# openSX70_ALADDIN_V398SEEED_20180219.net
KiCad netlist of a schematic drawn in EAGLE
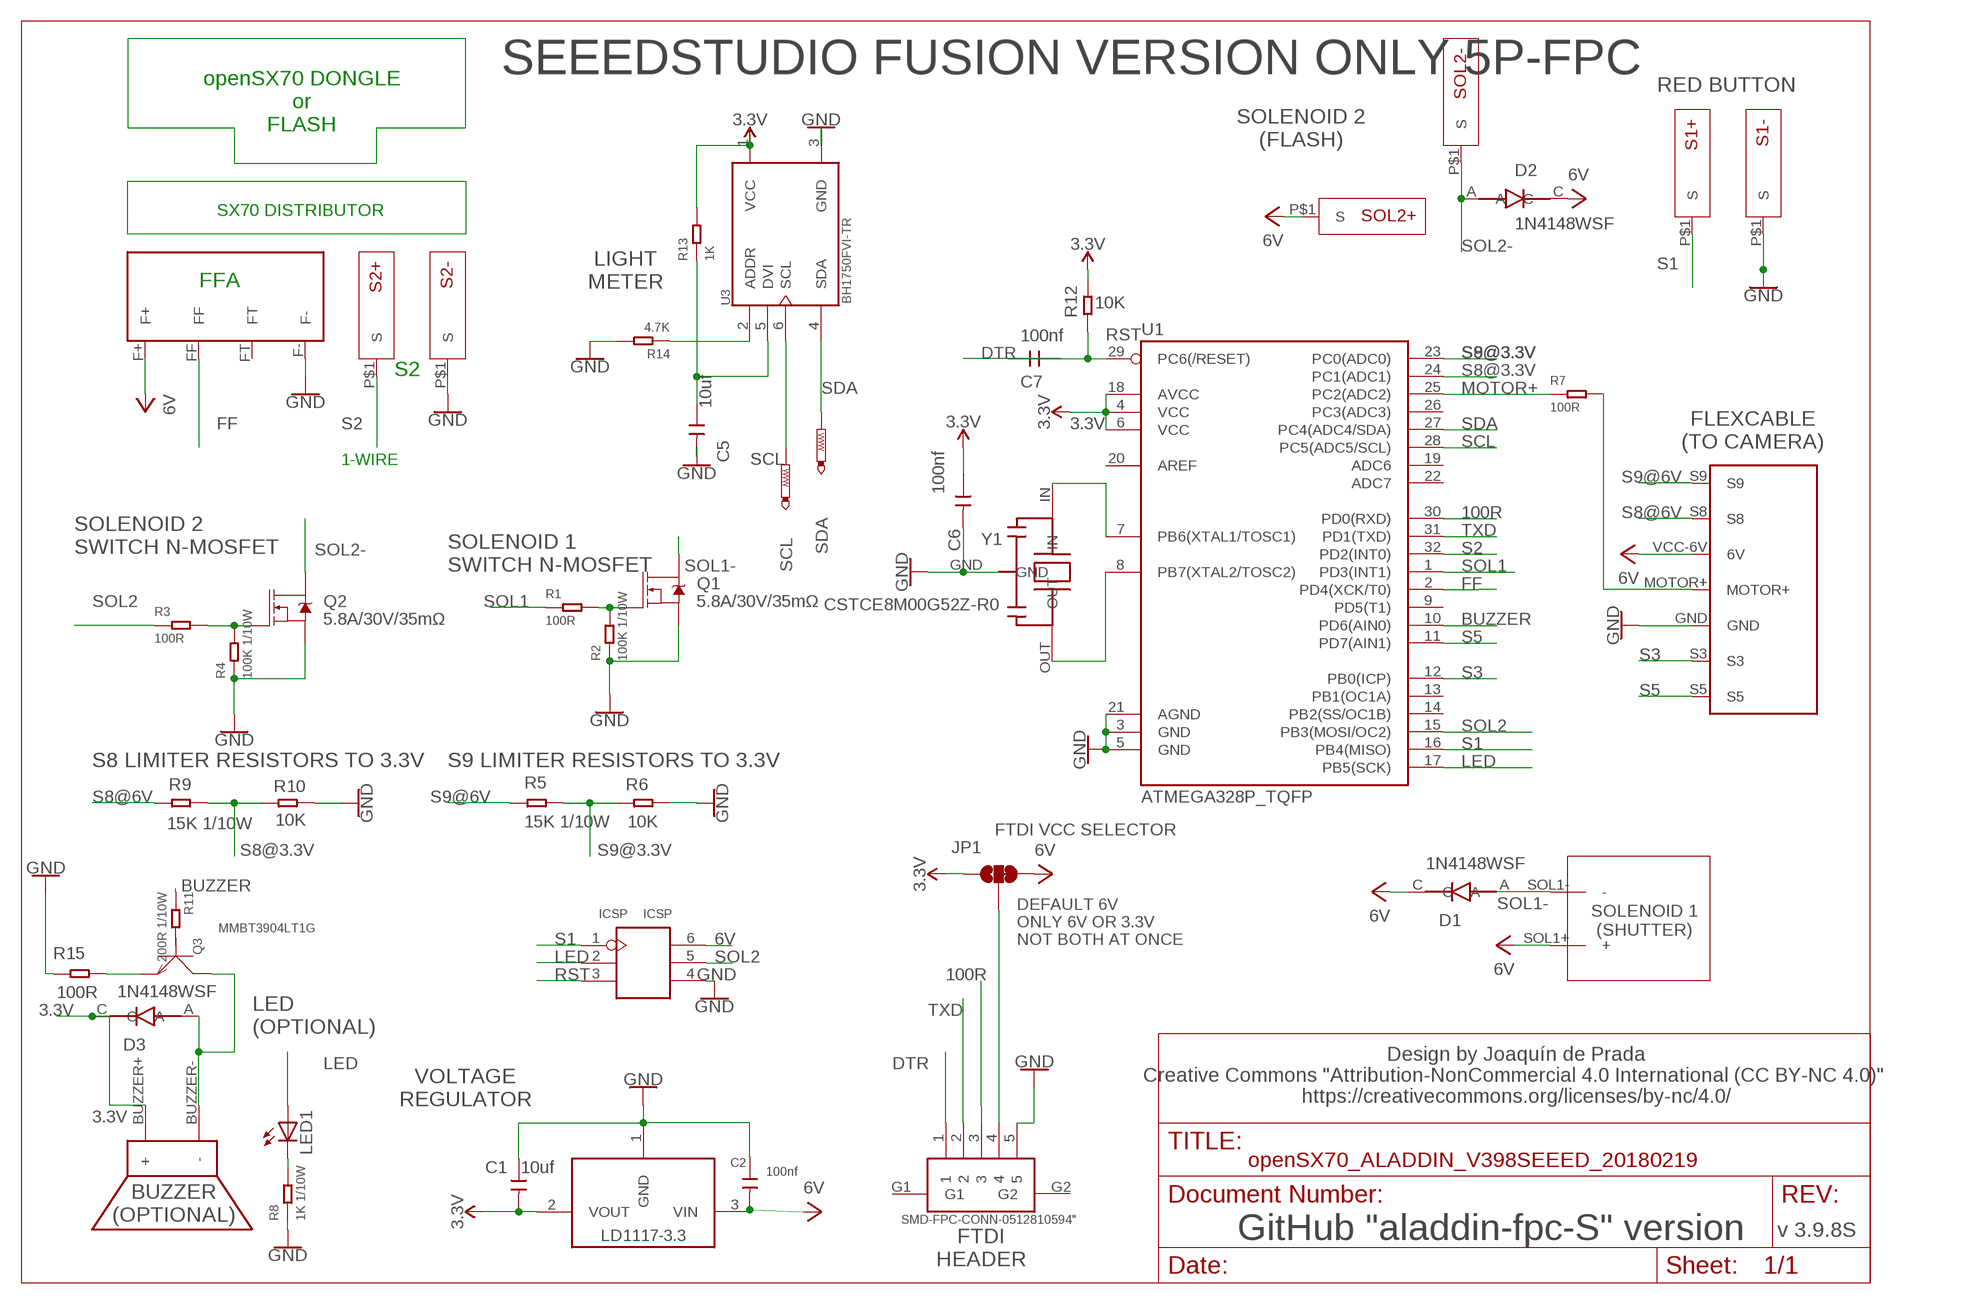
[diagram p0: schematic, sheet 1]

(export (version "E")
  (design (tool "Eeschema 10.0.6"))
  (components
    (comp (ref "C1")
      (value "10uf")
      (footprint "eagle-import:C0603")
      (fields (field (name "MPN") "CC0603KRX5R6BB106"))
      (libsource (lib "eagle-import") (part "CERAMIC-10UF-10V-10%-X5R(0603)"))
    )
    (comp (ref "C2")
      (value "100nf")
      (footprint "eagle-import:C0603")
      (fields (field (name "MPN") "CC0603KRX7R9BB104"))
      (libsource (lib "eagle-import") (part "CERAMIC-100NF-50V-10%-X7R(0603)"))
    )
    (comp (ref "C5")
      (value "10uf")
      (footprint "eagle-import:C0603")
      (fields (field (name "MPN") "CC0603KRX5R6BB106"))
      (libsource (lib "eagle-import") (part "CERAMIC-10UF-10V-10%-X5R(0603)"))
    )
    (comp (ref "C6")
      (value "100nf")
      (footprint "eagle-import:C0603")
      (fields (field (name "MPN") "CC0603KRX7R9BB104"))
      (libsource (lib "eagle-import") (part "CERAMIC-100NF-50V-10%-X7R(0603)"))
    )
    (comp (ref "C7")
      (value "100nf")
      (footprint "eagle-import:C0603")
      (fields (field (name "MPN") "CC0603KRX7R9BB104"))
      (libsource (lib "eagle-import") (part "CERAMIC-100NF-50V-10%-X7R(0603)"))
    )
    (comp (ref "D1")
      (value "1N4148WSF")
      (footprint "eagle-import:SODFL2512X100N")
      (fields (field (name "MANUFACTURER") "Fairchild Semiconductor"))
      (libsource (lib "eagle-import") (part "1N4148WS"))
    )
    (comp (ref "D2")
      (value "1N4148WSF")
      (footprint "eagle-import:SODFL2512X100N")
      (fields (field (name "MANUFACTURER") "Fairchild Semiconductor"))
      (libsource (lib "eagle-import") (part "1N4148WS"))
    )
    (comp (ref "D3")
      (value "1N4148WSF")
      (footprint "eagle-import:SODFL2512X100N")
      (fields (field (name "MANUFACTURER") "Fairchild Semiconductor"))
      (libsource (lib "eagle-import") (part "1N4148WS"))
    )
    (comp (ref "ICSP")
      (value "ICSP")
      (footprint "eagle-import:H2X3-2.54")
      (libsource (lib "eagle-import") (part "ICSP"))
    )
    (comp (ref "JP1")
      (value "FTDI VCC SELECTOR")
      (footprint "eagle-import:SMT-JUMPER_3_1-NC_TRACE_SILK")
      (libsource (lib "eagle-import") (part "JUMPER-SMT_3_1-NC_TRACE_SILK"))
    )
    (comp (ref "LD11172.5V")
      (value "LD1117 2.5V")
      (footprint "eagle-import:SOT223")
      (fields (field (name "MF") "Advanced Monolithic Systems") (field (name "MP") "AMS1117-5.0"))
      (libsource (lib "eagle-import") (part "LD1117-3.3"))
    )
    (comp (ref "LED1")
      (value "LEDCHIPLED_0805")
      (footprint "eagle-import:CHIPLED_0805")
      (libsource (lib "eagle-import") (part "LEDCHIPLED_0805"))
    )
    (comp (ref "Q1")
      (value "5.8A/30V/35mΩ")
      (footprint "eagle-import:SOT23-3")
      (libsource (lib "eagle-import") (part "MOSFET-NCH-AO3404A"))
    )
    (comp (ref "Q2")
      (value "5.8A/30V/35mΩ")
      (footprint "eagle-import:SOT23-3")
      (libsource (lib "eagle-import") (part "MOSFET-NCH-AO3404A"))
    )
    (comp (ref "Q3")
      (value "MMBT3904LT1G")
      (footprint "eagle-import:SOT-23")
      (libsource (lib "eagle-import") (part "SMD-TRANSISTORS-NPN-40V-200MA-MMBT3904LT1G(SOT-23)"))
    )
    (comp (ref "R1")
      (value "100R")
      (footprint "eagle-import:R0603")
      (fields (field (name "MPN") "RC0603JR-07100RL"))
      (libsource (lib "eagle-import") (part "SMD-RES-100R-5%-1/10W(0603)"))
    )
    (comp (ref "R2")
      (value "100K 1/10W")
      (footprint "eagle-import:R0603")
      (fields (field (name "MPN") "RC0603JR-07100KL"))
      (libsource (lib "eagle-import") (part "SMD-RES-100K-5%-1/10W(0603)"))
    )
    (comp (ref "R3")
      (value "100R")
      (footprint "eagle-import:R0603")
      (fields (field (name "MPN") "RC0603JR-07100RL"))
      (libsource (lib "eagle-import") (part "SMD-RES-100R-5%-1/10W(0603)"))
    )
    (comp (ref "R4")
      (value "100K 1/10W")
      (footprint "eagle-import:R0603")
      (fields (field (name "MPN") "RC0603JR-07100KL"))
      (libsource (lib "eagle-import") (part "SMD-RES-100K-5%-1/10W(0603)"))
    )
    (comp (ref "R5")
      (value "15K 1/10W")
      (footprint "eagle-import:R0603")
      (fields (field (name "MPN") "RC0603FR-0715KL"))
      (libsource (lib "eagle-import") (part "SMD-RES-15K-1%-1/10W(0603)"))
    )
    (comp (ref "R6")
      (value "10K")
      (footprint "eagle-import:R0603")
      (fields (field (name "MPN") "RC0603FR-0710KL"))
      (libsource (lib "eagle-import") (part "SMD-RES-10K-1%-1/10W(0603)"))
    )
    (comp (ref "R7")
      (value "100R")
      (footprint "eagle-import:R0603")
      (fields (field (name "MPN") "RC0603JR-07100RL"))
      (libsource (lib "eagle-import") (part "SMD-RES-100R-5%-1/10W(0603)"))
    )
    (comp (ref "R8")
      (value "1K 1/10W")
      (footprint "eagle-import:R0603")
      (fields (field (name "MPN") "RC0603JR-071KL"))
      (libsource (lib "eagle-import") (part "SMD-RES-1K-5%-1/10W(0603)"))
    )
    (comp (ref "R9")
      (value "15K 1/10W")
      (footprint "eagle-import:R0603")
      (fields (field (name "MPN") "RC0603FR-0715KL"))
      (libsource (lib "eagle-import") (part "SMD-RES-15K-1%-1/10W(0603)"))
    )
    (comp (ref "R10")
      (value "10K")
      (footprint "eagle-import:R0603")
      (fields (field (name "MPN") "RC0603FR-0710KL"))
      (libsource (lib "eagle-import") (part "SMD-RES-10K-1%-1/10W(0603)"))
    )
    (comp (ref "R11")
      (value "200R 1/10W")
      (footprint "eagle-import:R0603")
      (fields (field (name "MPN") "RC0603JR-07200RL"))
      (libsource (lib "eagle-import") (part "SMD-RES-200R-5%-1/10W(0603)"))
    )
    (comp (ref "R12")
      (value "10K")
      (footprint "eagle-import:R0603")
      (fields (field (name "MPN") "RC0603FR-0710KL"))
      (libsource (lib "eagle-import") (part "SMD-RES-10K-1%-1/10W(0603)"))
    )
    (comp (ref "R13")
      (value "1K")
      (footprint "eagle-import:R0603")
      (fields (field (name "MPN") "RC0603FR-071KL"))
      (libsource (lib "eagle-import") (part "SMD-RES-1K-1%-1/10W(0603)"))
    )
    (comp (ref "R14")
      (value "4.7K")
      (footprint "eagle-import:R0603")
      (fields (field (name "MPN") "RC0603JR-074K7L"))
      (libsource (lib "eagle-import") (part "SMD-RES-4.7K-5%-1/10W(0603)"))
    )
    (comp (ref "R15")
      (value "100R")
      (footprint "eagle-import:R0603")
      (fields (field (name "MPN") "RC0603JR-07100RL"))
      (libsource (lib "eagle-import") (part "SMD-RES-100R-5%-1/10W(0603)"))
    )
    (comp (ref "S1+")
      (value "SX70-S-PAD-NEW")
      (footprint "eagle-import:SX70-S-PAD2")
      (libsource (lib "eagle-import") (part "SX70-S-PAD-NEW"))
    )
    (comp (ref "S1-")
      (value "SX70-S-PAD-NEW")
      (footprint "eagle-import:SX70-S-PAD2")
      (libsource (lib "eagle-import") (part "SX70-S-PAD-NEW"))
    )
    (comp (ref "S2+")
      (value "SX70-S-PAD-NEW")
      (footprint "eagle-import:SX70-S-PAD2")
      (libsource (lib "eagle-import") (part "SX70-S-PAD-NEW"))
    )
    (comp (ref "S2-")
      (value "SX70-S-PAD-NEW")
      (footprint "eagle-import:SX70-S-PAD2")
      (libsource (lib "eagle-import") (part "SX70-S-PAD-NEW"))
    )
    (comp (ref "SCL")
      (value "PTR1TP08R")
      (footprint "eagle-import:TP08R")
      (libsource (lib "eagle-import") (part "PTR1TP08R"))
    )
    (comp (ref "SDA")
      (value "PTR1TP08R")
      (footprint "eagle-import:TP08R")
      (libsource (lib "eagle-import") (part "PTR1TP08R"))
    )
    (comp (ref "SOL1")
      (value "SX70-SOLENOID1-2PADS")
      (footprint "eagle-import:SX70-SOLENOID1-2")
      (libsource (lib "eagle-import") (part "SX70-SOLENOID1-2PADS"))
    )
    (comp (ref "SOL2+")
      (value "SX70-S-PAD-NEW")
      (footprint "eagle-import:SX70-S-PAD2")
      (libsource (lib "eagle-import") (part "SX70-S-PAD-NEW"))
    )
    (comp (ref "SOL2-")
      (value "SX70-S-PAD-NEW")
      (footprint "eagle-import:SX70-S-PAD2")
      (libsource (lib "eagle-import") (part "SX70-S-PAD-NEW"))
    )
    (comp (ref "U$1")
      (value "SX70-7-PAD")
      (footprint "eagle-import:SX70-7-PAD")
      (libsource (lib "eagle-import") (part "SX70-7-PAD"))
    )
    (comp (ref "U$2")
      (value "FFA")
      (footprint "eagle-import:FFA-PAD-PACKAGE")
      (libsource (lib "eagle-import") (part "SX70-FFA-PAD"))
    )
    (comp (ref "U$3")
      (value "CSET8-5G_V2")
      (footprint "eagle-import:CSET8-5G_PACKAGE")
      (libsource (lib "eagle-import") (part "CSET8-5G_V2"))
    )
    (comp (ref "U$4")
      (value "SMD-FPC-CONN-0512810594\"")
      (footprint "eagle-import:51281-0594")
      (libsource (lib "eagle-import") (part "SMD-FPC-CONN-0512810594{dblquote}"))
    )
    (comp (ref "U1")
      (value "ATMEGA328P_TQFP")
      (footprint "eagle-import:TQFP32-08")
      (libsource (lib "eagle-import") (part "ATMEGA328P_TQFP"))
    )
    (comp (ref "U3")
      (value "BH1750FVI-TR")
      (footprint "eagle-import:SOTFL50P300X75-6N")
      (fields (field (name "MF") "Rohm"))
      (libsource (lib "eagle-import") (part "BH1750FVI-TR"))
    )
    (comp (ref "Y1")
      (value "CSTCE8M00G52Z-R0")
      (footprint "eagle-import:CFP95P160X100-3N")
      (fields (field (name "MF") "Murata") (field (name "MP") "CSTCE16M0V53-R0"))
      (libsource (lib "eagle-import") (part "CSTCE16M0V53-R0"))
    )
  )
  (nets
    (net (code "1") (name "/100R") (class "Default")
      (node (ref "U$4") (pin "3") (pinfunction "3_3") (pintype "bidirectional"))
      (node (ref "U1") (pin "30") (pinfunction "PD0(RXD)_30") (pintype "bidirectional"))
    )
    (net (code "2") (name "/BUZZER") (class "Default")
      (node (ref "R11") (pin "1") (pinfunction "1_1") (pintype "passive"))
      (node (ref "U1") (pin "10") (pinfunction "PD6(AIN0)_10") (pintype "bidirectional"))
    )
    (net (code "3") (name "/DTR") (class "Default")
      (node (ref "C7") (pin "1") (pinfunction "1_1") (pintype "passive"))
      (node (ref "U$4") (pin "1") (pinfunction "1_1") (pintype "bidirectional"))
    )
    (net (code "4") (name "/FF") (class "Default")
      (node (ref "U$2") (pin "FF") (pinfunction "FF_FF") (pintype "bidirectional"))
      (node (ref "U1") (pin "2") (pinfunction "PD4(XCK/T0)_2") (pintype "bidirectional"))
    )
    (net (code "5") (name "/LED") (class "Default")
      (node (ref "ICSP") (pin "2") (pinfunction "SCK_2") (pintype "bidirectional"))
      (node (ref "LED1") (pin "A") (pinfunction "A_A") (pintype "passive"))
      (node (ref "U1") (pin "17") (pinfunction "PB5(SCK)_17") (pintype "bidirectional"))
    )
    (net (code "6") (name "/MOTOR+") (class "Default")
      (node (ref "R7") (pin "1") (pinfunction "1_1") (pintype "passive"))
      (node (ref "U1") (pin "25") (pinfunction "PC2(ADC2)_25") (pintype "bidirectional"))
    )
    (net (code "7") (name "/RST") (class "Default")
      (node (ref "C7") (pin "2") (pinfunction "2_2") (pintype "passive"))
      (node (ref "ICSP") (pin "3") (pinfunction "RST_3") (pintype "bidirectional"))
      (node (ref "R12") (pin "1") (pinfunction "1_1") (pintype "passive"))
      (node (ref "U1") (pin "29") (pinfunction "PC6(/RESET)_29") (pintype "bidirectional"))
    )
    (net (code "8") (name "/S1") (class "Default")
      (node (ref "ICSP") (pin "1") (pinfunction "MISO_1") (pintype "bidirectional"))
      (node (ref "S1+") (pin "P$1") (pinfunction "S_P$1") (pintype "bidirectional"))
      (node (ref "U1") (pin "16") (pinfunction "PB4(MISO)_16") (pintype "bidirectional"))
    )
    (net (code "9") (name "/S2") (class "Default")
      (node (ref "S2+") (pin "P$1") (pinfunction "S_P$1") (pintype "bidirectional"))
      (node (ref "U1") (pin "32") (pinfunction "PD2(INT0)_32") (pintype "bidirectional"))
    )
    (net (code "10") (name "/S3") (class "Default")
      (node (ref "U$1") (pin "S3") (pinfunction "S3_S3") (pintype "bidirectional"))
      (node (ref "U1") (pin "12") (pinfunction "PB0(ICP)_12") (pintype "bidirectional"))
    )
    (net (code "11") (name "/S5") (class "Default")
      (node (ref "U$1") (pin "S5") (pinfunction "S5_S5") (pintype "bidirectional"))
      (node (ref "U1") (pin "11") (pinfunction "PD7(AIN1)_11") (pintype "bidirectional"))
    )
    (net (code "12") (name "/S8@3.3V") (class "Default")
      (node (ref "R10") (pin "1") (pinfunction "1_1") (pintype "passive"))
      (node (ref "R9") (pin "2") (pinfunction "2_2") (pintype "passive"))
      (node (ref "U1") (pin "24") (pinfunction "PC1(ADC1)_24") (pintype "bidirectional"))
    )
    (net (code "13") (name "/S8@6V") (class "Default")
      (node (ref "R9") (pin "1") (pinfunction "1_1") (pintype "passive"))
      (node (ref "U$1") (pin "S8") (pinfunction "S8_S8") (pintype "bidirectional"))
    )
    (net (code "14") (name "/S9@3.3V") (class "Default")
      (node (ref "R5") (pin "2") (pinfunction "2_2") (pintype "passive"))
      (node (ref "R6") (pin "1") (pinfunction "1_1") (pintype "passive"))
      (node (ref "U1") (pin "23") (pinfunction "PC0(ADC0)_23") (pintype "bidirectional"))
    )
    (net (code "15") (name "/S9@6V") (class "Default")
      (node (ref "R5") (pin "1") (pinfunction "1_1") (pintype "passive"))
      (node (ref "U$1") (pin "S9") (pinfunction "S9_S9") (pintype "bidirectional"))
    )
    (net (code "16") (name "/SCL") (class "Default")
      (node (ref "SCL") (pin "TP") (pinfunction "TP_TP") (pintype "input"))
      (node (ref "U1") (pin "28") (pinfunction "PC5(ADC5/SCL)_28") (pintype "bidirectional"))
      (node (ref "U3") (pin "6") (pinfunction "SCL_6") (pintype "input"))
    )
    (net (code "17") (name "/SDA") (class "Default")
      (node (ref "SDA") (pin "TP") (pinfunction "TP_TP") (pintype "input"))
      (node (ref "U1") (pin "27") (pinfunction "PC4(ADC4/SDA)_27") (pintype "bidirectional"))
      (node (ref "U3") (pin "4") (pinfunction "SDA_4") (pintype "bidirectional"))
    )
    (net (code "18") (name "/SOL1") (class "Default")
      (node (ref "R1") (pin "1") (pinfunction "1_1") (pintype "passive"))
      (node (ref "U1") (pin "1") (pinfunction "PD3(INT1)_1") (pintype "bidirectional"))
    )
    (net (code "19") (name "/SOL1-") (class "Default")
      (node (ref "D1") (pin "A") (pinfunction "A_A") (pintype "passive"))
      (node (ref "Q1") (pin "3") (pinfunction "D_3") (pintype "bidirectional"))
      (node (ref "SOL1") (pin "SOL1-") (pinfunction "-_SOL1-") (pintype "bidirectional"))
    )
    (net (code "20") (name "/SOL2") (class "Default")
      (node (ref "ICSP") (pin "5") (pinfunction "MOSI_5") (pintype "bidirectional"))
      (node (ref "R3") (pin "1") (pinfunction "1_1") (pintype "passive"))
      (node (ref "U1") (pin "15") (pinfunction "PB3(MOSI/OC2)_15") (pintype "bidirectional"))
    )
    (net (code "21") (name "/SOL2-") (class "Default")
      (node (ref "D2") (pin "A") (pinfunction "A_A") (pintype "passive"))
      (node (ref "Q2") (pin "3") (pinfunction "D_3") (pintype "bidirectional"))
      (node (ref "SOL2-") (pin "P$1") (pinfunction "S_P$1") (pintype "bidirectional"))
    )
    (net (code "22") (name "/TXD") (class "Default")
      (node (ref "U$4") (pin "2") (pinfunction "2_2") (pintype "bidirectional"))
      (node (ref "U1") (pin "31") (pinfunction "PD1(TXD)_31") (pintype "bidirectional"))
    )
    (net (code "23") (name "3.3V") (class "Default")
      (node (ref "C1") (pin "2") (pinfunction "2_2") (pintype "passive"))
      (node (ref "C6") (pin "1") (pinfunction "1_1") (pintype "passive"))
      (node (ref "D3") (pin "C") (pinfunction "C_C") (pintype "passive"))
      (node (ref "JP1") (pin "1") (pinfunction "1_1") (pintype "passive"))
      (node (ref "LD11172.5V") (pin "2") (pinfunction "VOUT_2") (pintype "bidirectional"))
      (node (ref "R12") (pin "2") (pinfunction "2_2") (pintype "passive"))
      (node (ref "R13") (pin "2") (pinfunction "2_2") (pintype "passive"))
      (node (ref "U$3") (pin "BUZZER+") (pinfunction "+_BUZZER+") (pintype "bidirectional"))
      (node (ref "U1") (pin "18") (pinfunction "AVCC_18") (pintype "bidirectional"))
      (node (ref "U1") (pin "4") (pinfunction "VCC_4") (pintype "bidirectional"))
      (node (ref "U1") (pin "6") (pinfunction "VCC_6") (pintype "bidirectional"))
      (node (ref "U3") (pin "1") (pinfunction "VCC_1") (pintype "power_in"))
    )
    (net (code "24") (name "6V") (class "Default")
      (node (ref "C2") (pin "2") (pinfunction "2_2") (pintype "passive"))
      (node (ref "D1") (pin "C") (pinfunction "C_C") (pintype "passive"))
      (node (ref "D2") (pin "C") (pinfunction "C_C") (pintype "passive"))
      (node (ref "ICSP") (pin "6") (pinfunction "VCC_6") (pintype "bidirectional"))
      (node (ref "JP1") (pin "3") (pinfunction "3_3") (pintype "passive"))
      (node (ref "LD11172.5V") (pin "3") (pinfunction "VIN_3") (pintype "bidirectional"))
      (node (ref "SOL1") (pin "SOL1+") (pinfunction "+_SOL1+") (pintype "bidirectional"))
      (node (ref "SOL2+") (pin "P$1") (pinfunction "S_P$1") (pintype "bidirectional"))
      (node (ref "U$1") (pin "VCC-6V") (pinfunction "6V_VCC-6V") (pintype "bidirectional"))
      (node (ref "U$2") (pin "F+") (pinfunction "F+_F+") (pintype "bidirectional"))
    )
    (net (code "25") (name "GND") (class "Default")
      (node (ref "C1") (pin "1") (pinfunction "1_1") (pintype "passive"))
      (node (ref "C2") (pin "1") (pinfunction "1_1") (pintype "passive"))
      (node (ref "C5") (pin "2") (pinfunction "2_2") (pintype "passive"))
      (node (ref "C6") (pin "2") (pinfunction "2_2") (pintype "passive"))
      (node (ref "ICSP") (pin "4") (pinfunction "GND_4") (pintype "bidirectional"))
      (node (ref "LD11172.5V") (pin "1") (pinfunction "GND_1") (pintype "bidirectional"))
      (node (ref "Q1") (pin "2") (pinfunction "S_2") (pintype "bidirectional"))
      (node (ref "Q2") (pin "2") (pinfunction "S_2") (pintype "bidirectional"))
      (node (ref "R10") (pin "2") (pinfunction "2_2") (pintype "passive"))
      (node (ref "R14") (pin "2") (pinfunction "2_2") (pintype "passive"))
      (node (ref "R15") (pin "1") (pinfunction "1_1") (pintype "passive"))
      (node (ref "R2") (pin "1") (pinfunction "1_1") (pintype "passive"))
      (node (ref "R4") (pin "1") (pinfunction "1_1") (pintype "passive"))
      (node (ref "R6") (pin "2") (pinfunction "2_2") (pintype "passive"))
      (node (ref "R8") (pin "1") (pinfunction "1_1") (pintype "passive"))
      (node (ref "S1-") (pin "P$1") (pinfunction "S_P$1") (pintype "bidirectional"))
      (node (ref "S2-") (pin "P$1") (pinfunction "S_P$1") (pintype "bidirectional"))
      (node (ref "U$1") (pin "GND") (pinfunction "GND_GND") (pintype "bidirectional"))
      (node (ref "U$2") (pin "F-") (pinfunction "F-_F-") (pintype "bidirectional"))
      (node (ref "U$4") (pin "5") (pinfunction "5_5") (pintype "bidirectional"))
      (node (ref "U1") (pin "21") (pinfunction "AGND_21") (pintype "bidirectional"))
      (node (ref "U1") (pin "3") (pinfunction "GND_3") (pintype "bidirectional"))
      (node (ref "U1") (pin "5") (pinfunction "GND_5") (pintype "bidirectional"))
      (node (ref "U3") (pin "3") (pinfunction "GND_3") (pintype "power_in"))
      (node (ref "Y1") (pin "GND") (pinfunction "GND_GND") (pintype "passive"))
    )
    (net (code "26") (name "Net-(JP1-Pad2)") (class "Default")
      (node (ref "JP1") (pin "2") (pinfunction "2_2") (pintype "passive"))
      (node (ref "U$4") (pin "4") (pinfunction "4_4") (pintype "bidirectional"))
    )
    (net (code "27") (name "Net-(LED1-PadC)") (class "Default")
      (node (ref "LED1") (pin "C") (pinfunction "C_C") (pintype "passive"))
      (node (ref "R8") (pin "2") (pinfunction "2_2") (pintype "passive"))
    )
    (net (code "28") (name "Net-(Q1-G)") (class "Default")
      (node (ref "Q1") (pin "1") (pinfunction "G_1") (pintype "bidirectional"))
      (node (ref "R1") (pin "2") (pinfunction "2_2") (pintype "passive"))
      (node (ref "R2") (pin "2") (pinfunction "2_2") (pintype "passive"))
    )
    (net (code "29") (name "Net-(Q2-G)") (class "Default")
      (node (ref "Q2") (pin "1") (pinfunction "G_1") (pintype "bidirectional"))
      (node (ref "R3") (pin "2") (pinfunction "2_2") (pintype "passive"))
      (node (ref "R4") (pin "2") (pinfunction "2_2") (pintype "passive"))
    )
    (net (code "30") (name "Net-(Q3-B)") (class "Default")
      (node (ref "Q3") (pin "1") (pinfunction "B_1") (pintype "passive"))
      (node (ref "R11") (pin "2") (pinfunction "2_2") (pintype "passive"))
    )
    (net (code "31") (name "Net-(Q3-C)") (class "Default")
      (node (ref "D3") (pin "A") (pinfunction "A_A") (pintype "passive"))
      (node (ref "Q3") (pin "3") (pinfunction "C_3") (pintype "passive"))
      (node (ref "U$3") (pin "BUZZER-") (pinfunction "-_BUZZER-") (pintype "bidirectional"))
    )
    (net (code "32") (name "Net-(Q3-E)") (class "Default")
      (node (ref "Q3") (pin "2") (pinfunction "E_2") (pintype "passive"))
      (node (ref "R15") (pin "2") (pinfunction "2_2") (pintype "passive"))
    )
    (net (code "33") (name "Net-(R7-Pad2)") (class "Default")
      (node (ref "R7") (pin "2") (pinfunction "2_2") (pintype "passive"))
      (node (ref "U$1") (pin "MOTOR+") (pinfunction "MOTOR+_MOTOR+") (pintype "bidirectional"))
    )
    (net (code "34") (name "Net-(U1-PB6(XTAL1{slash}TOSC1))") (class "Default")
      (node (ref "U1") (pin "7") (pinfunction "PB6(XTAL1/TOSC1)_7") (pintype "bidirectional"))
      (node (ref "Y1") (pin "IN") (pinfunction "IN_IN") (pintype "input"))
    )
    (net (code "35") (name "Net-(U1-PB7(XTAL2{slash}TOSC2))") (class "Default")
      (node (ref "U1") (pin "8") (pinfunction "PB7(XTAL2/TOSC2)_8") (pintype "bidirectional"))
      (node (ref "Y1") (pin "OUT") (pinfunction "OUT_OUT") (pintype "output"))
    )
    (net (code "36") (name "Net-(U3-ADDR)") (class "Default")
      (node (ref "R14") (pin "1") (pinfunction "1_1") (pintype "passive"))
      (node (ref "U3") (pin "2") (pinfunction "ADDR_2") (pintype "input"))
    )
    (net (code "37") (name "Net-(U3-DVI)") (class "Default")
      (node (ref "C5") (pin "1") (pinfunction "1_1") (pintype "passive"))
      (node (ref "R13") (pin "1") (pinfunction "1_1") (pintype "passive"))
      (node (ref "U3") (pin "5") (pinfunction "DVI_5") (pintype "input"))
    )
    (net (code "38") (name "unconnected-(U$2-PadFT)") (class "Default")
      (node (ref "U$2") (pin "FT") (pinfunction "FT_FT") (pintype "bidirectional"))
    )
    (net (code "39") (name "unconnected-(U$4-PadG1)") (class "Default")
      (node (ref "U$4") (pin "G1") (pinfunction "G1_G1") (pintype "bidirectional"))
    )
    (net (code "40") (name "unconnected-(U$4-PadG2)") (class "Default")
      (node (ref "U$4") (pin "G2") (pinfunction "G2_G2") (pintype "bidirectional"))
    )
    (net (code "41") (name "unconnected-(U1-ADC6-Pad19)") (class "Default")
      (node (ref "U1") (pin "19") (pinfunction "ADC6_19") (pintype "bidirectional"))
    )
    (net (code "42") (name "unconnected-(U1-ADC7-Pad22)") (class "Default")
      (node (ref "U1") (pin "22") (pinfunction "ADC7_22") (pintype "bidirectional"))
    )
    (net (code "43") (name "unconnected-(U1-AREF-Pad20)") (class "Default")
      (node (ref "U1") (pin "20") (pinfunction "AREF_20") (pintype "bidirectional"))
    )
    (net (code "44") (name "unconnected-(U1-PB1(OC1A)-Pad13)") (class "Default")
      (node (ref "U1") (pin "13") (pinfunction "PB1(OC1A)_13") (pintype "bidirectional"))
    )
    (net (code "45") (name "unconnected-(U1-PB2(SS{slash}OC1B)-Pad14)") (class "Default")
      (node (ref "U1") (pin "14") (pinfunction "PB2(SS/OC1B)_14") (pintype "bidirectional"))
    )
    (net (code "46") (name "unconnected-(U1-PC3(ADC3)-Pad26)") (class "Default")
      (node (ref "U1") (pin "26") (pinfunction "PC3(ADC3)_26") (pintype "bidirectional"))
    )
    (net (code "47") (name "unconnected-(U1-PD5(T1)-Pad9)") (class "Default")
      (node (ref "U1") (pin "9") (pinfunction "PD5(T1)_9") (pintype "bidirectional"))
    )
  )
)
